# Sheet1.net
KiCad netlist of a schematic drawn in Altium Designer
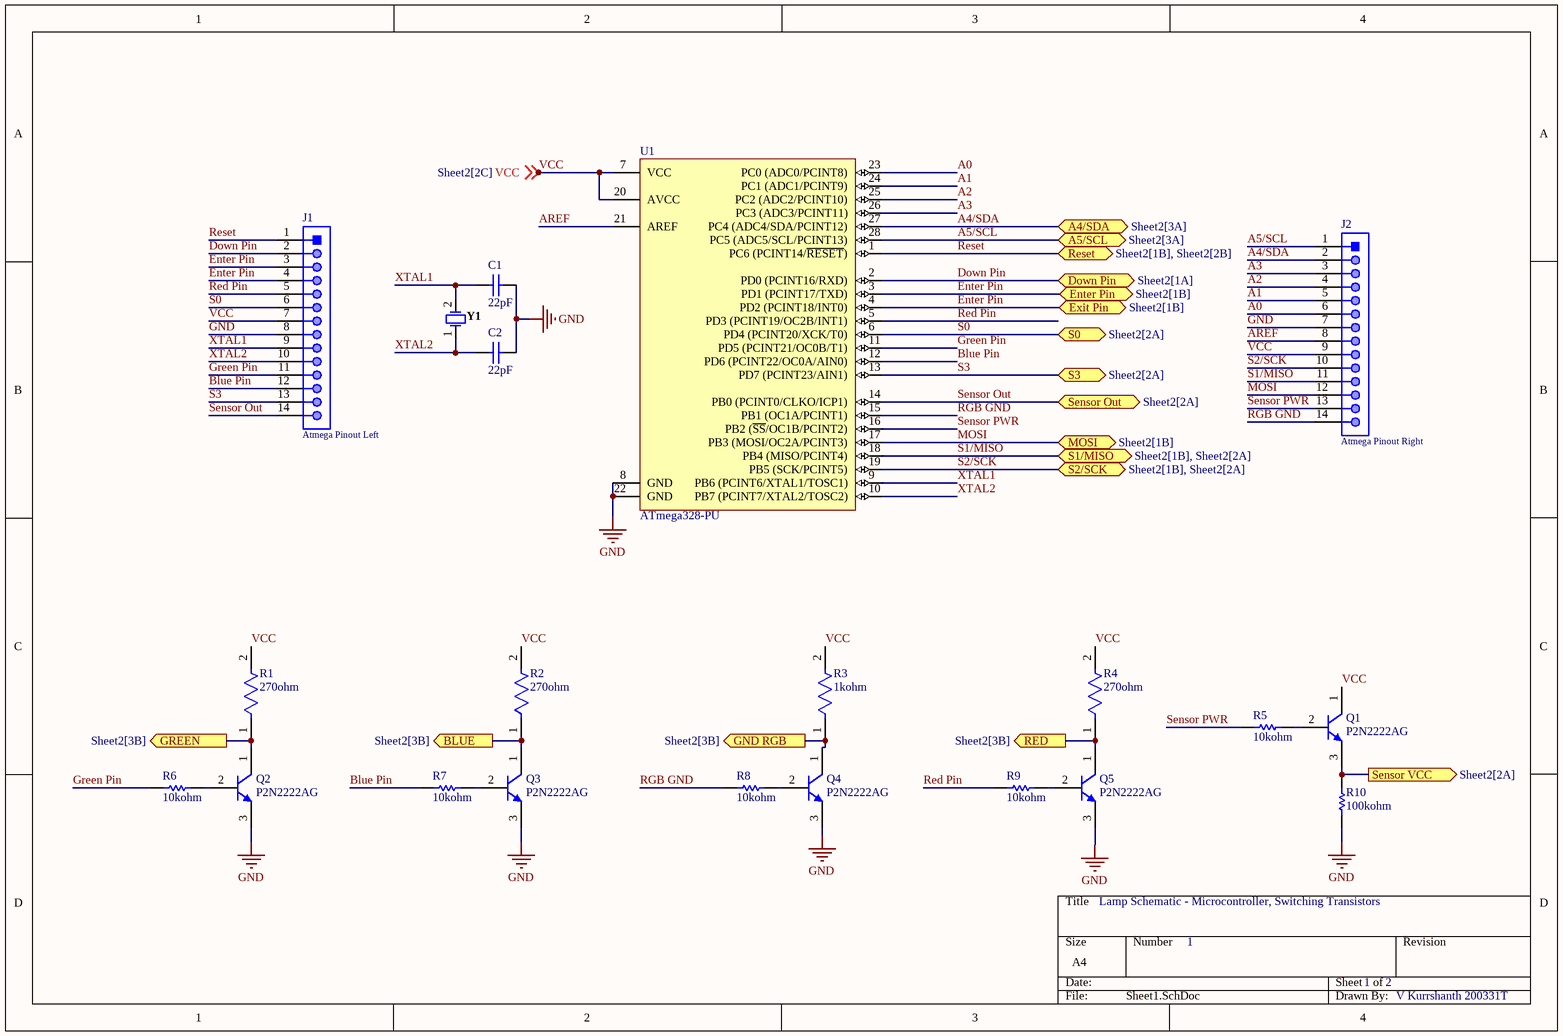
[diagram p0: Sheet1.SchDoc]

(export (version "E")
  (design (tool "Eeschema 10.0.6"))
  (components
    (comp (ref "C1")
      (value "22pF")
      (footprint "KEMT-C315-THT-2")
      (description "Capacitor, Ceramic, 22 pF, +/-10 %, 100 V, -55 to 125 degC, 2-Pin THD, RoHS, Bulk")
      (libsource (lib "Altium Content Vault") (part "CAP-NP-2"))
    )
    (comp (ref "C2")
      (value "22pF")
      (footprint "KEMT-C315-THT-2")
      (description "Capacitor, Ceramic, 22 pF, +/-10 %, 100 V, -55 to 125 degC, 2-Pin THD, RoHS, Bulk")
      (libsource (lib "Altium Content Vault") (part "CAP-NP-2"))
    )
    (comp (ref "J1")
      (value "Atmega Pinout Left")
      (footprint "61301411121")
      (description "THT Vertical Pin Header WR-PHD, Pitch 2.54 mm, Single Row, 14 pins")
      (fields
        (field (name "MANUFACTURER") "Wurth Elektronik")
        (field (name "PART NUMBER") "61301411121")
        (field (name "PUBLISHER") "WurthElektronik")
      )
      (libsource (lib "Altium Content Vault") (part "WE-CN-1P-M-R14"))
    )
    (comp (ref "J2")
      (value "Atmega Pinout Right")
      (footprint "61301411121")
      (description "THT Vertical Pin Header WR-PHD, Pitch 2.54 mm, Single Row, 14 pins")
      (fields
        (field (name "MANUFACTURER") "Wurth Elektronik")
        (field (name "PART NUMBER") "61301411121")
        (field (name "PUBLISHER") "WurthElektronik")
      )
      (libsource (lib "Altium Content Vault") (part "WE-CN-1P-M-R14"))
    )
    (comp (ref "Q1")
      (value "P2N2222AG")
      (footprint "ONSC-TO-92-3-29-11")
      (description "Amplifier Transistor, NPN Silicon, 3-Pin TO-92, Pb-Free, Bulk Box")
      (fields (field (name "MANUFACTURER") "On Semiconductor"))
      (libsource (lib "Altium Content Vault") (part "ONSC-NPN-C1B2E3-3"))
    )
    (comp (ref "Q2")
      (value "P2N2222AG")
      (footprint "ONSC-TO-92-3-29-11")
      (description "Amplifier Transistor, NPN Silicon, 3-Pin TO-92, Pb-Free, Bulk Box")
      (fields (field (name "MANUFACTURER") "On Semiconductor"))
      (libsource (lib "Altium Content Vault") (part "ONSC-NPN-C1B2E3-3"))
    )
    (comp (ref "Q3")
      (value "P2N2222AG")
      (footprint "ONSC-TO-92-3-29-11")
      (description "Amplifier Transistor, NPN Silicon, 3-Pin TO-92, Pb-Free, Bulk Box")
      (fields (field (name "MANUFACTURER") "On Semiconductor"))
      (libsource (lib "Altium Content Vault") (part "ONSC-NPN-C1B2E3-3"))
    )
    (comp (ref "Q4")
      (value "P2N2222AG")
      (footprint "ONSC-TO-92-3-29-11")
      (description "Amplifier Transistor, NPN Silicon, 3-Pin TO-92, Pb-Free, Bulk Box")
      (fields (field (name "MANUFACTURER") "On Semiconductor"))
      (libsource (lib "Altium Content Vault") (part "ONSC-NPN-C1B2E3-3"))
    )
    (comp (ref "Q5")
      (value "P2N2222AG")
      (footprint "ONSC-TO-92-3-29-11")
      (description "Amplifier Transistor, NPN Silicon, 3-Pin TO-92, Pb-Free, Bulk Box")
      (fields (field (name "MANUFACTURER") "On Semiconductor"))
      (libsource (lib "Altium Content Vault") (part "ONSC-NPN-C1B2E3-3"))
    )
    (comp (ref "R1")
      (value "270ohm")
      (footprint "FP-CFR50J2K2-MFG")
      (description "RES 270 OHM 5% 1/2W AXIAL")
      (fields (field (name "TOLERANCE") "5%"))
      (libsource (lib "Altium Content Vault") (part "1029c3af85768c4190bb7ad29bc67b5"))
    )
    (comp (ref "R2")
      (value "270ohm")
      (footprint "FP-CFR50J2K2-MFG")
      (description "RES 270 OHM 5% 1/2W AXIAL")
      (fields (field (name "TOLERANCE") "5%"))
      (libsource (lib "Altium Content Vault") (part "1029c3af85768c4190bb7ad29bc67b5"))
    )
    (comp (ref "R3")
      (value "1kohm")
      (footprint "FP-CFR50J2K2-MFG")
      (description "RES 1k OHM 5% 1/2W AXIAL")
      (fields (field (name "TOLERANCE") "5%"))
      (libsource (lib "Altium Content Vault") (part "1029c3af85768c4190bb7ad29bc67b5"))
    )
    (comp (ref "R4")
      (value "270ohm")
      (footprint "FP-CFR50J2K2-MFG")
      (description "RES 270 OHM 5% 1/2W AXIAL")
      (fields (field (name "TOLERANCE") "5%"))
      (libsource (lib "Altium Content Vault") (part "1029c3af85768c4190bb7ad29bc67b5"))
    )
    (comp (ref "R5")
      (value "10kohm")
      (footprint "RESA60-630X240")
      (description "Axial Resistor, 10 KOhm, +/- 1%, 0.25 W, -55 to 155 degC, 2-Pin THD, RoHS, Bulk")
      (fields (field (name "TOLERANCE") "1%") (field (name "MANUFACTURER") "Yageo"))
      (libsource (lib "Altium Content Vault") (part "RES-2"))
    )
    (comp (ref "R6")
      (value "10kohm")
      (footprint "RESA60-630X240")
      (description "Axial Resistor, 10 KOhm, +/- 1%, 0.25 W, -55 to 155 degC, 2-Pin THD, RoHS, Bulk")
      (fields (field (name "TOLERANCE") "1%") (field (name "MANUFACTURER") "Yageo"))
      (libsource (lib "Altium Content Vault") (part "RES-2"))
    )
    (comp (ref "R7")
      (value "10kohm")
      (footprint "RESA60-630X240")
      (description "Axial Resistor, 10 KOhm, +/- 1%, 0.25 W, -55 to 155 degC, 2-Pin THD, RoHS, Bulk")
      (fields (field (name "TOLERANCE") "1%") (field (name "MANUFACTURER") "Yageo"))
      (libsource (lib "Altium Content Vault") (part "RES-2"))
    )
    (comp (ref "R8")
      (value "10kohm")
      (footprint "RESA60-630X240")
      (description "Axial Resistor, 10 KOhm, +/- 1%, 0.25 W, -55 to 155 degC, 2-Pin THD, RoHS, Bulk")
      (fields (field (name "TOLERANCE") "1%") (field (name "MANUFACTURER") "Yageo"))
      (libsource (lib "Altium Content Vault") (part "RES-2"))
    )
    (comp (ref "R9")
      (value "10kohm")
      (footprint "RESA60-630X240")
      (description "Axial Resistor, 10 KOhm, +/- 1%, 0.25 W, -55 to 155 degC, 2-Pin THD, RoHS, Bulk")
      (fields (field (name "TOLERANCE") "1%") (field (name "MANUFACTURER") "Yageo"))
      (libsource (lib "Altium Content Vault") (part "RES-2"))
    )
    (comp (ref "R10")
      (value "100kohm")
      (footprint "RESA60-630X240")
      (description "Axial Resistor, 100 KOhm, +/- 1%, 0.25 W, -55 to 155 degC, 2-Pin THD, RoHS, Bulk")
      (fields (field (name "TOLERANCE") "1%") (field (name "MANUFACTURER") "Yageo"))
      (libsource (lib "Altium Content Vault") (part "RES-2"))
    )
    (comp (ref "U1")
      (value "ATmega328-PU")
      (footprint "28P3")
      (libsource (lib "Altium Content Vault") (part "MC-8B-ATM48-IL28"))
    )
    (comp (ref "Y1")
      (value "FOXSLF/160-20")
      (footprint "FOX-FOXSLF160-20")
      (description "Resistance Weld Thru-Hole Crystal, 16 MHz, -20 to 70 degC, 2-Pin THD, RoHS, Bulk")
      (fields (field (name "TOLERANCE") "1%"))
      (libsource (lib "Altium Content Vault") (part "XTAL-1-2-2"))
    )
  )
  (nets
    (net (code "1") (name "/A0") (class "Default")
      (node (ref "J2") (pin "6") (pinfunction "6_6") (pintype "passive"))
      (node (ref "U1") (pin "23") (pinfunction "PC0_(ADC0/PCINT8)_23") (pintype "bidirectional"))
    )
    (net (code "2") (name "/A1") (class "Default")
      (node (ref "J2") (pin "5") (pinfunction "5_5") (pintype "passive"))
      (node (ref "U1") (pin "24") (pinfunction "PC1_(ADC1/PCINT9)_24") (pintype "bidirectional"))
    )
    (net (code "3") (name "/A2") (class "Default")
      (node (ref "J2") (pin "4") (pinfunction "4_4") (pintype "passive"))
      (node (ref "U1") (pin "25") (pinfunction "PC2_(ADC2/PCINT10)_25") (pintype "bidirectional"))
    )
    (net (code "4") (name "/A3") (class "Default")
      (node (ref "J2") (pin "3") (pinfunction "3_3") (pintype "passive"))
      (node (ref "U1") (pin "26") (pinfunction "PC3_(ADC3/PCINT11)_26") (pintype "bidirectional"))
    )
    (net (code "5") (name "/A4{slash}SDA") (class "Default")
      (node (ref "J2") (pin "2") (pinfunction "2_2") (pintype "passive"))
      (node (ref "U1") (pin "27") (pinfunction "PC4_(ADC4/SDA/PCINT12)_27") (pintype "bidirectional"))
    )
    (net (code "6") (name "/A5{slash}SCL") (class "Default")
      (node (ref "J2") (pin "1") (pinfunction "1_1") (pintype "passive"))
      (node (ref "U1") (pin "28") (pinfunction "PC5_(ADC5/SCL/PCINT13)_28") (pintype "bidirectional"))
    )
    (net (code "7") (name "/AREF") (class "Default")
      (node (ref "J2") (pin "8") (pinfunction "8_8") (pintype "passive"))
      (node (ref "U1") (pin "21") (pinfunction "AREF_21") (pintype "power_in"))
    )
    (net (code "8") (name "/BLUE") (class "Default")
      (node (ref "Q3") (pin "1") (pinfunction "C_1") (pintype "passive"))
      (node (ref "R2") (pin "1") (pinfunction "1_1") (pintype "passive"))
    )
    (net (code "9") (name "/Blue Pin") (class "Default")
      (node (ref "J1") (pin "12") (pinfunction "12_12") (pintype "passive"))
      (node (ref "R7") (pin "1") (pinfunction "1_1") (pintype "passive"))
      (node (ref "U1") (pin "12") (pinfunction "PD6_(PCINT22/OC0A/AIN0)_12") (pintype "bidirectional"))
    )
    (net (code "10") (name "/Down Pin") (class "Default")
      (node (ref "J1") (pin "2") (pinfunction "2_2") (pintype "passive"))
      (node (ref "U1") (pin "2") (pinfunction "PD0_(PCINT16/RXD)_2") (pintype "bidirectional"))
    )
    (net (code "11") (name "/Enter Pin") (class "Default")
      (node (ref "J1") (pin "3") (pinfunction "3_3") (pintype "passive"))
      (node (ref "J1") (pin "4") (pinfunction "4_4") (pintype "passive"))
      (node (ref "U1") (pin "3") (pinfunction "PD1_(PCINT17/TXD)_3") (pintype "bidirectional"))
      (node (ref "U1") (pin "4") (pinfunction "PD2_(PCINT18/INT0)_4") (pintype "bidirectional"))
    )
    (net (code "12") (name "/GND RGB") (class "Default")
      (node (ref "Q4") (pin "1") (pinfunction "C_1") (pintype "passive"))
      (node (ref "R3") (pin "1") (pinfunction "1_1") (pintype "passive"))
    )
    (net (code "13") (name "/GREEN") (class "Default")
      (node (ref "Q2") (pin "1") (pinfunction "C_1") (pintype "passive"))
      (node (ref "R1") (pin "1") (pinfunction "1_1") (pintype "passive"))
    )
    (net (code "14") (name "/Green Pin") (class "Default")
      (node (ref "J1") (pin "11") (pinfunction "11_11") (pintype "passive"))
      (node (ref "R6") (pin "1") (pinfunction "1_1") (pintype "passive"))
      (node (ref "U1") (pin "11") (pinfunction "PD5_(PCINT21/OC0B/T1)_11") (pintype "bidirectional"))
    )
    (net (code "15") (name "/MOSI") (class "Default")
      (node (ref "J2") (pin "12") (pinfunction "12_12") (pintype "passive"))
      (node (ref "U1") (pin "17") (pinfunction "PB3_(MOSI/OC2A/PCINT3)_17") (pintype "bidirectional"))
    )
    (net (code "16") (name "/RED") (class "Default")
      (node (ref "Q5") (pin "1") (pinfunction "C_1") (pintype "passive"))
      (node (ref "R4") (pin "1") (pinfunction "1_1") (pintype "passive"))
    )
    (net (code "17") (name "/RGB GND") (class "Default")
      (node (ref "J2") (pin "14") (pinfunction "14_14") (pintype "passive"))
      (node (ref "R8") (pin "1") (pinfunction "1_1") (pintype "passive"))
      (node (ref "U1") (pin "15") (pinfunction "PB1_(OC1A/PCINT1)_15") (pintype "bidirectional"))
    )
    (net (code "18") (name "/Red Pin") (class "Default")
      (node (ref "J1") (pin "5") (pinfunction "5_5") (pintype "passive"))
      (node (ref "R9") (pin "1") (pinfunction "1_1") (pintype "passive"))
      (node (ref "U1") (pin "5") (pinfunction "PD3_(PCINT19/OC2B/INT1)_5") (pintype "bidirectional"))
    )
    (net (code "19") (name "/Reset") (class "Default")
      (node (ref "J1") (pin "1") (pinfunction "1_1") (pintype "passive"))
      (node (ref "U1") (pin "1") (pinfunction "PC6_(PCINT14/~{RESET})_1") (pintype "bidirectional"))
    )
    (net (code "20") (name "/S0") (class "Default")
      (node (ref "J1") (pin "6") (pinfunction "6_6") (pintype "passive"))
      (node (ref "U1") (pin "6") (pinfunction "PD4_(PCINT20/XCK/T0)_6") (pintype "bidirectional"))
    )
    (net (code "21") (name "/S1{slash}MISO") (class "Default")
      (node (ref "J2") (pin "11") (pinfunction "11_11") (pintype "passive"))
      (node (ref "U1") (pin "18") (pinfunction "PB4_(MISO/PCINT4)_18") (pintype "bidirectional"))
    )
    (net (code "22") (name "/S2{slash}SCK") (class "Default")
      (node (ref "J2") (pin "10") (pinfunction "10_10") (pintype "passive"))
      (node (ref "U1") (pin "19") (pinfunction "PB5_(SCK/PCINT5)_19") (pintype "bidirectional"))
    )
    (net (code "23") (name "/S3") (class "Default")
      (node (ref "J1") (pin "13") (pinfunction "13_13") (pintype "passive"))
      (node (ref "U1") (pin "13") (pinfunction "PD7_(PCINT23/AIN1)_13") (pintype "bidirectional"))
    )
    (net (code "24") (name "/Sensor Out") (class "Default")
      (node (ref "J1") (pin "14") (pinfunction "14_14") (pintype "passive"))
      (node (ref "U1") (pin "14") (pinfunction "PB0_(PCINT0/CLKO/ICP1)_14") (pintype "bidirectional"))
    )
    (net (code "25") (name "/Sensor PWR") (class "Default")
      (node (ref "J2") (pin "13") (pinfunction "13_13") (pintype "passive"))
      (node (ref "R5") (pin "1") (pinfunction "1_1") (pintype "passive"))
      (node (ref "U1") (pin "16") (pinfunction "PB2_(~{SS}/OC1B/PCINT2)_16") (pintype "bidirectional"))
    )
    (net (code "26") (name "/Sensor VCC") (class "Default")
      (node (ref "Q1") (pin "3") (pinfunction "E_3") (pintype "passive"))
      (node (ref "R10") (pin "2") (pinfunction "2_2") (pintype "passive"))
    )
    (net (code "27") (name "/XTAL1") (class "Default")
      (node (ref "C1") (pin "1") (pinfunction "1_1") (pintype "passive"))
      (node (ref "J1") (pin "9") (pinfunction "9_9") (pintype "passive"))
      (node (ref "U1") (pin "9") (pinfunction "PB6_(PCINT6/XTAL1/TOSC1)_9") (pintype "bidirectional"))
      (node (ref "Y1") (pin "2") (pinfunction "2_2") (pintype "passive"))
    )
    (net (code "28") (name "/XTAL2") (class "Default")
      (node (ref "C2") (pin "1") (pinfunction "1_1") (pintype "passive"))
      (node (ref "J1") (pin "10") (pinfunction "10_10") (pintype "passive"))
      (node (ref "U1") (pin "10") (pinfunction "PB7_(PCINT7/XTAL2/TOSC2)_10") (pintype "bidirectional"))
      (node (ref "Y1") (pin "1") (pinfunction "1_1") (pintype "passive"))
    )
    (net (code "29") (name "GND") (class "Default")
      (node (ref "C1") (pin "2") (pinfunction "2_2") (pintype "passive"))
      (node (ref "C2") (pin "2") (pinfunction "2_2") (pintype "passive"))
      (node (ref "J1") (pin "8") (pinfunction "8_8") (pintype "passive"))
      (node (ref "J2") (pin "7") (pinfunction "7_7") (pintype "passive"))
      (node (ref "Q2") (pin "3") (pinfunction "E_3") (pintype "passive"))
      (node (ref "Q3") (pin "3") (pinfunction "E_3") (pintype "passive"))
      (node (ref "Q4") (pin "3") (pinfunction "E_3") (pintype "passive"))
      (node (ref "Q5") (pin "3") (pinfunction "E_3") (pintype "passive"))
      (node (ref "R10") (pin "1") (pinfunction "1_1") (pintype "passive"))
      (node (ref "U1") (pin "22") (pinfunction "GND_22") (pintype "power_in"))
      (node (ref "U1") (pin "8") (pinfunction "GND_8") (pintype "power_in"))
    )
    (net (code "30") (name "Net-(Q1-B)") (class "Default")
      (node (ref "Q1") (pin "2") (pinfunction "B_2") (pintype "passive"))
      (node (ref "R5") (pin "2") (pinfunction "2_2") (pintype "passive"))
    )
    (net (code "31") (name "Net-(Q2-B)") (class "Default")
      (node (ref "Q2") (pin "2") (pinfunction "B_2") (pintype "passive"))
      (node (ref "R6") (pin "2") (pinfunction "2_2") (pintype "passive"))
    )
    (net (code "32") (name "Net-(Q3-B)") (class "Default")
      (node (ref "Q3") (pin "2") (pinfunction "B_2") (pintype "passive"))
      (node (ref "R7") (pin "2") (pinfunction "2_2") (pintype "passive"))
    )
    (net (code "33") (name "Net-(Q4-B)") (class "Default")
      (node (ref "Q4") (pin "2") (pinfunction "B_2") (pintype "passive"))
      (node (ref "R8") (pin "2") (pinfunction "2_2") (pintype "passive"))
    )
    (net (code "34") (name "Net-(Q5-B)") (class "Default")
      (node (ref "Q5") (pin "2") (pinfunction "B_2") (pintype "passive"))
      (node (ref "R9") (pin "2") (pinfunction "2_2") (pintype "passive"))
    )
    (net (code "35") (name "VCC") (class "Default")
      (node (ref "J1") (pin "7") (pinfunction "7_7") (pintype "passive"))
      (node (ref "J2") (pin "9") (pinfunction "9_9") (pintype "passive"))
      (node (ref "Q1") (pin "1") (pinfunction "C_1") (pintype "passive"))
      (node (ref "R1") (pin "2") (pinfunction "2_2") (pintype "passive"))
      (node (ref "R2") (pin "2") (pinfunction "2_2") (pintype "passive"))
      (node (ref "R3") (pin "2") (pinfunction "2_2") (pintype "passive"))
      (node (ref "R4") (pin "2") (pinfunction "2_2") (pintype "passive"))
      (node (ref "U1") (pin "20") (pinfunction "AVCC_20") (pintype "power_in"))
      (node (ref "U1") (pin "7") (pinfunction "VCC_7") (pintype "power_in"))
    )
  )
)
